# Codeshelf-0008.net
KiCad netlist of a schematic drawn in EAGLE
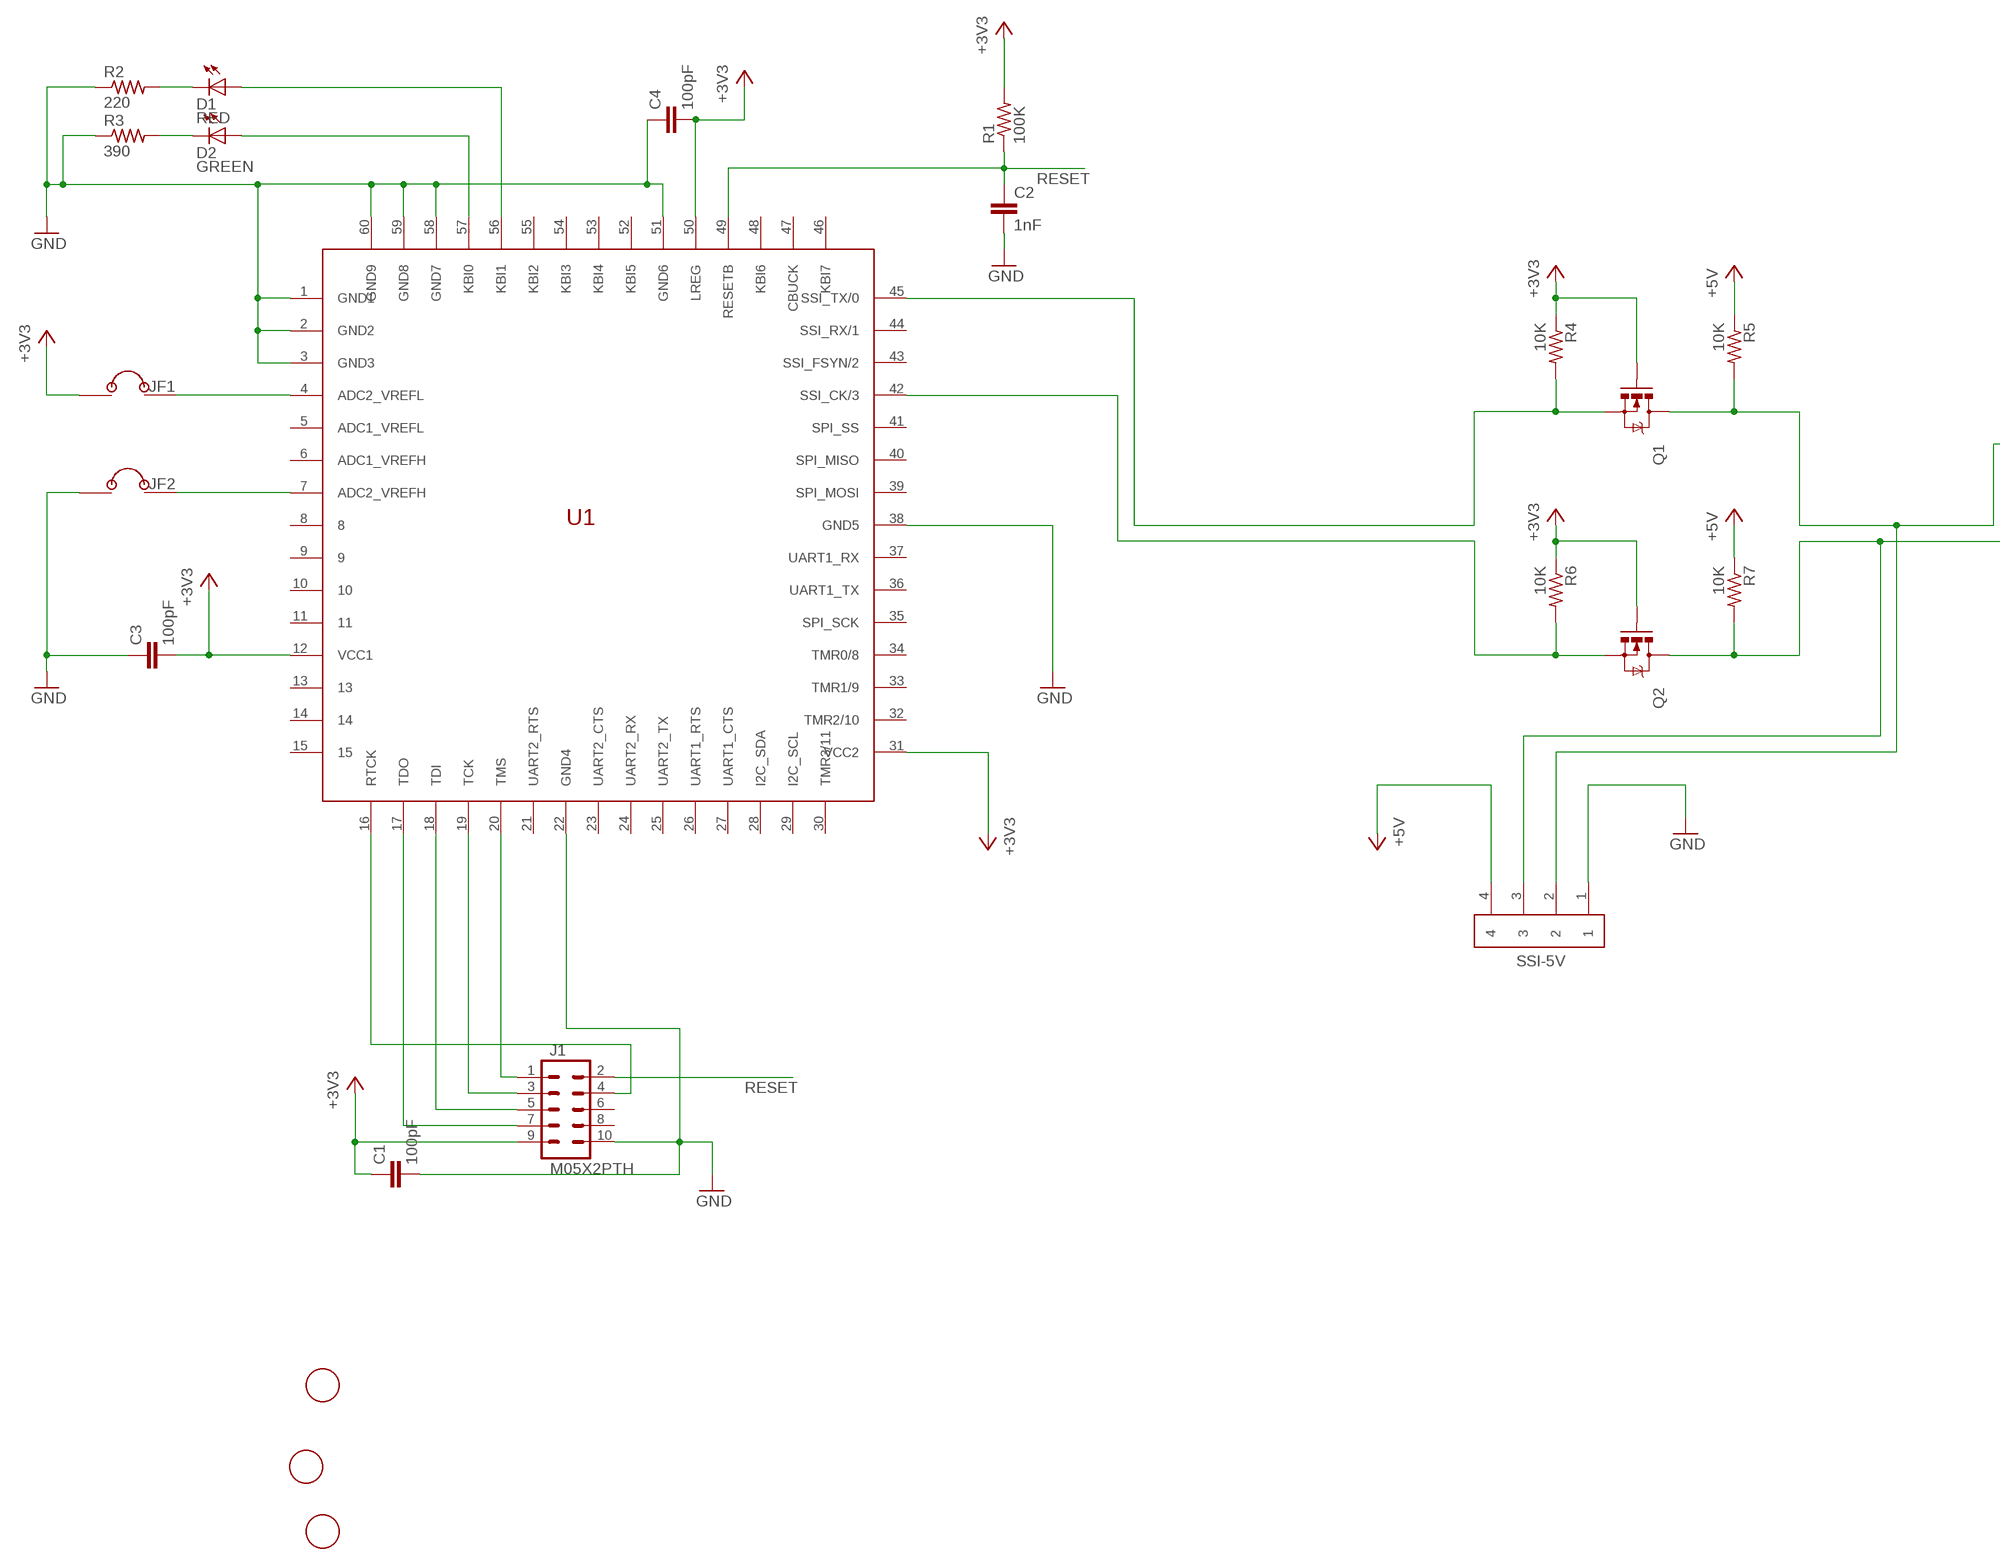
[diagram p0: schematic, sheet 1, part 1 of 2]
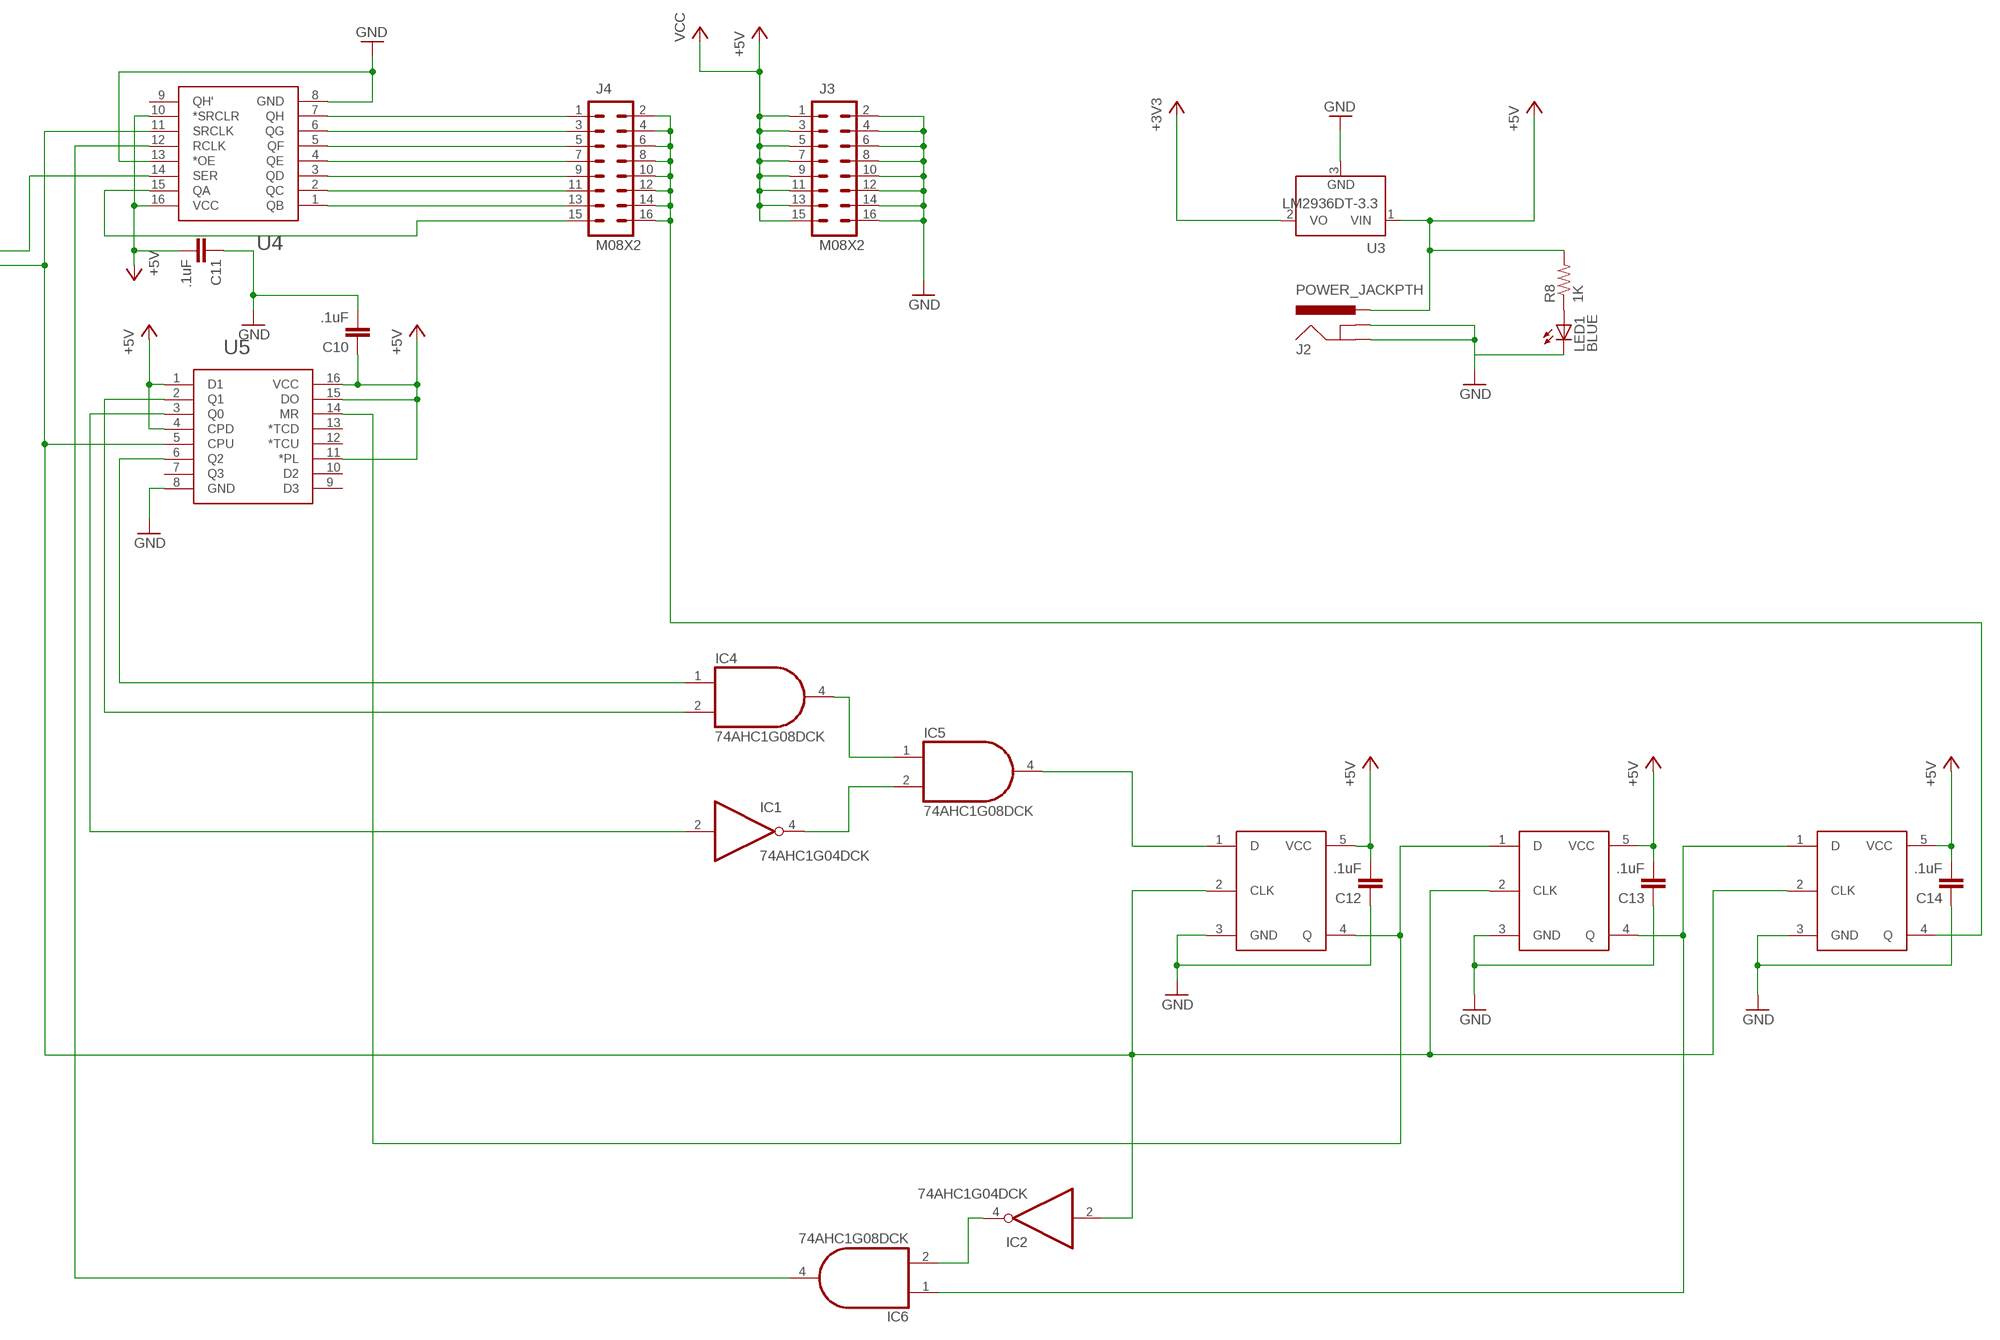
[diagram p1: schematic, sheet 1, part 2 of 2]

(export (version "E")
  (design (tool "Eeschema 10.0.6"))
  (components
    (comp (ref "C1")
      (value "100pF")
      (footprint "eagle-import:C0603")
      (libsource (lib "eagle-import") (part "RF-C0603"))
    )
    (comp (ref "C2")
      (value "1nF")
      (footprint "eagle-import:C0603")
      (libsource (lib "eagle-import") (part "RF-C0603"))
    )
    (comp (ref "C3")
      (value "100pF")
      (footprint "eagle-import:C0603")
      (libsource (lib "eagle-import") (part "RF-C0603"))
    )
    (comp (ref "C4")
      (value "100pF")
      (footprint "eagle-import:C0603")
      (libsource (lib "eagle-import") (part "RF-C0603"))
    )
    (comp (ref "C10")
      (value ".1uF")
      (footprint "eagle-import:C0402")
      (libsource (lib "eagle-import") (part "RF-C0402"))
    )
    (comp (ref "C11")
      (value ".1uF")
      (footprint "eagle-import:C0402")
      (libsource (lib "eagle-import") (part "RF-C0402"))
    )
    (comp (ref "C12")
      (value ".1uF")
      (footprint "eagle-import:C0402")
      (libsource (lib "eagle-import") (part "RF-C0402"))
    )
    (comp (ref "C13")
      (value ".1uF")
      (footprint "eagle-import:C0402")
      (libsource (lib "eagle-import") (part "RF-C0402"))
    )
    (comp (ref "C14")
      (value ".1uF")
      (footprint "eagle-import:C0402")
      (libsource (lib "eagle-import") (part "RF-C0402"))
    )
    (comp (ref "D1")
      (value "RED")
      (footprint "eagle-import:CHIP-LED0805")
      (libsource (lib "eagle-import") (part "LEDCHIP-LED0805"))
    )
    (comp (ref "D2")
      (value "GREEN")
      (footprint "eagle-import:CHIP-LED0805")
      (libsource (lib "eagle-import") (part "LEDCHIP-LED0805"))
    )
    (comp (ref "IC1")
      (value "74AHC1G04DCK")
      (footprint "eagle-import:SC70-5")
      (libsource (lib "eagle-import") (part "741G04DCKAHC"))
    )
    (comp (ref "IC2")
      (value "74AHC1G04DCK")
      (footprint "eagle-import:SC70-5")
      (libsource (lib "eagle-import") (part "741G04DCKAHC"))
    )
    (comp (ref "IC4")
      (value "74AHC1G08DCK")
      (footprint "eagle-import:SC70-5")
      (libsource (lib "eagle-import") (part "741G08DCKAHC"))
    )
    (comp (ref "IC5")
      (value "74AHC1G08DCK")
      (footprint "eagle-import:SC70-5")
      (libsource (lib "eagle-import") (part "741G08DCKAHC"))
    )
    (comp (ref "IC6")
      (value "74AHC1G08DCK")
      (footprint "eagle-import:SC70-5")
      (libsource (lib "eagle-import") (part "741G08DCKAHC"))
    )
    (comp (ref "J1")
      (value "M05X2PTH")
      (footprint "eagle-import:AVR_ICSP")
      (libsource (lib "eagle-import") (part "M05X2PTH"))
    )
    (comp (ref "J2")
      (value "POWER_JACKPTH")
      (footprint "eagle-import:POWER_JACK_PTH")
      (libsource (lib "eagle-import") (part "POWER_JACKPTH"))
    )
    (comp (ref "J3")
      (value "M08X2")
      (footprint "eagle-import:2X8")
      (libsource (lib "eagle-import") (part "M08X2"))
    )
    (comp (ref "J4")
      (value "M08X2")
      (footprint "eagle-import:2X8")
      (libsource (lib "eagle-import") (part "M08X2"))
    )
    (comp (ref "JF1")
      (value "JUMPER-2X-SMT-VIA")
      (footprint "eagle-import:JUMPER-VIA-2X")
      (libsource (lib "eagle-import") (part "JUMPER-2X-SMT-VIA"))
    )
    (comp (ref "JF2")
      (value "JUMPER-2X-SMT-VIA")
      (footprint "eagle-import:JUMPER-VIA-2X")
      (libsource (lib "eagle-import") (part "JUMPER-2X-SMT-VIA"))
    )
    (comp (ref "LED1")
      (value "BLUE")
      (footprint "eagle-import:LED5MM")
      (libsource (lib "eagle-import") (part "LED5MM"))
    )
    (comp (ref "Q1")
      (value "MOSFET-NCHANNELBSS138")
      (footprint "eagle-import:SOT23")
      (libsource (lib "eagle-import") (part "MOSFET-NCHANNELBSS138"))
    )
    (comp (ref "Q2")
      (value "MOSFET-NCHANNELBSS138")
      (footprint "eagle-import:SOT23")
      (libsource (lib "eagle-import") (part "MOSFET-NCHANNELBSS138"))
    )
    (comp (ref "R1")
      (value "100K")
      (footprint "eagle-import:RF-R0402")
      (libsource (lib "eagle-import") (part "RF-R0402"))
    )
    (comp (ref "R2")
      (value "220")
      (footprint "eagle-import:RF-R0402")
      (libsource (lib "eagle-import") (part "RF-R0402"))
    )
    (comp (ref "R3")
      (value "390")
      (footprint "eagle-import:RF-R0402")
      (libsource (lib "eagle-import") (part "RF-R0402"))
    )
    (comp (ref "R4")
      (value "10K")
      (footprint "eagle-import:RF-R0402")
      (libsource (lib "eagle-import") (part "RF-R0402"))
    )
    (comp (ref "R5")
      (value "10K")
      (footprint "eagle-import:RF-R0402")
      (libsource (lib "eagle-import") (part "RF-R0402"))
    )
    (comp (ref "R6")
      (value "10K")
      (footprint "eagle-import:RF-R0402")
      (libsource (lib "eagle-import") (part "RF-R0402"))
    )
    (comp (ref "R7")
      (value "10K")
      (footprint "eagle-import:RF-R0402")
      (libsource (lib "eagle-import") (part "RF-R0402"))
    )
    (comp (ref "R8")
      (value "1K")
      (footprint "eagle-import:0204_7")
      (libsource (lib "eagle-import") (part "R-US_0204/7"))
    )
    (comp (ref "SSI-5V")
      (value "HEADER-4X39357")
      (footprint "eagle-import:MOLEX-39357-0004")
      (libsource (lib "eagle-import") (part "HEADER-4X39357"))
    )
    (comp (ref "U$2")
      (value "FIDUCIAL")
      (footprint "eagle-import:FIDUCIAL_1MM")
      (libsource (lib "eagle-import") (part "FIDUCIAL"))
    )
    (comp (ref "U$3")
      (value "FIDUCIAL")
      (footprint "eagle-import:FIDUCIAL_1MM")
      (libsource (lib "eagle-import") (part "FIDUCIAL"))
    )
    (comp (ref "U$4")
      (value "FIDUCIAL")
      (footprint "eagle-import:FIDUCIAL_1MM")
      (libsource (lib "eagle-import") (part "FIDUCIAL"))
    )
    (comp (ref "U1")
      (value "ZSFM201-1A")
      (footprint "eagle-import:ZSFM201-1")
      (libsource (lib "eagle-import") (part "ZSFM201-1A"))
    )
    (comp (ref "U3")
      (value "LM2936DT-3.3")
      (footprint "eagle-import:TO252")
      (fields (field (name "MPN") "LM2936DT-3.3."))
      (libsource (lib "eagle-import") (part "LM2936?DT-3.3"))
    )
    (comp (ref "U4")
      (value "SN74HC595PW")
      (footprint "eagle-import:TSSOP16")
      (libsource (lib "eagle-import") (part "SN74HC595PW"))
    )
    (comp (ref "U5")
      (value "74HCT193PW")
      (footprint "eagle-import:TSSOP16")
      (libsource (lib "eagle-import") (part "74HCT193PW"))
    )
    (comp (ref "U6")
      (value "D-FLIP-FLOP-74LV1G79DBVR")
      (footprint "eagle-import:SOT23-5")
      (libsource (lib "eagle-import") (part "D-FLIP-FLOP-74LV1G79DBVR"))
    )
    (comp (ref "U7")
      (value "D-FLIP-FLOP-74LV1G79DBVR")
      (footprint "eagle-import:SOT23-5")
      (libsource (lib "eagle-import") (part "D-FLIP-FLOP-74LV1G79DBVR"))
    )
    (comp (ref "U8")
      (value "D-FLIP-FLOP-74LV1G79DBVR")
      (footprint "eagle-import:SOT23-5")
      (libsource (lib "eagle-import") (part "D-FLIP-FLOP-74LV1G79DBVR"))
    )
  )
  (nets
    (net (code "1") (name "+3V3") (class "Default")
      (node (ref "C1") (pin "1") (pinfunction "1_1") (pintype "passive"))
      (node (ref "C3") (pin "2") (pinfunction "2_2") (pintype "passive"))
      (node (ref "C4") (pin "2") (pinfunction "2_2") (pintype "passive"))
      (node (ref "J1") (pin "9") (pinfunction "9_9") (pintype "passive"))
      (node (ref "JF1") (pin "1") (pinfunction "1_1") (pintype "bidirectional"))
      (node (ref "Q1") (pin "1") (pinfunction "G_1") (pintype "passive"))
      (node (ref "Q2") (pin "1") (pinfunction "G_1") (pintype "passive"))
      (node (ref "R1") (pin "2") (pinfunction "2_2") (pintype "passive"))
      (node (ref "R4") (pin "1") (pinfunction "1_1") (pintype "passive"))
      (node (ref "R6") (pin "1") (pinfunction "1_1") (pintype "passive"))
      (node (ref "U1") (pin "12") (pinfunction "VCC1_12") (pintype "power_in"))
      (node (ref "U1") (pin "31") (pinfunction "VCC2_31") (pintype "power_in"))
      (node (ref "U1") (pin "50") (pinfunction "LREG_50") (pintype "bidirectional"))
      (node (ref "U3") (pin "2") (pinfunction "VO_2") (pintype "passive"))
    )
    (net (code "2") (name "+5V") (class "Default")
      (node (ref "C10") (pin "1") (pinfunction "1_1") (pintype "passive"))
      (node (ref "C11") (pin "2") (pinfunction "2_2") (pintype "passive"))
      (node (ref "C12") (pin "2") (pinfunction "2_2") (pintype "passive"))
      (node (ref "C13") (pin "2") (pinfunction "2_2") (pintype "passive"))
      (node (ref "C14") (pin "2") (pinfunction "2_2") (pintype "passive"))
      (node (ref "J2") (pin "PWR") (pinfunction "PWR_PWR") (pintype "bidirectional"))
      (node (ref "J3") (pin "1") (pinfunction "1_1") (pintype "passive"))
      (node (ref "J3") (pin "11") (pinfunction "11_11") (pintype "passive"))
      (node (ref "J3") (pin "13") (pinfunction "13_13") (pintype "passive"))
      (node (ref "J3") (pin "15") (pinfunction "15_15") (pintype "passive"))
      (node (ref "J3") (pin "3") (pinfunction "3_3") (pintype "passive"))
      (node (ref "J3") (pin "5") (pinfunction "5_5") (pintype "passive"))
      (node (ref "J3") (pin "7") (pinfunction "7_7") (pintype "passive"))
      (node (ref "J3") (pin "9") (pinfunction "9_9") (pintype "passive"))
      (node (ref "R5") (pin "1") (pinfunction "1_1") (pintype "passive"))
      (node (ref "R7") (pin "1") (pinfunction "1_1") (pintype "passive"))
      (node (ref "R8") (pin "2") (pinfunction "2_2") (pintype "passive"))
      (node (ref "SSI-5V") (pin "4") (pinfunction "4_4") (pintype "bidirectional"))
      (node (ref "U3") (pin "1") (pinfunction "VIN_1") (pintype "input"))
      (node (ref "U4") (pin "10") (pinfunction "*SRCLR_10") (pintype "bidirectional"))
      (node (ref "U4") (pin "16") (pinfunction "VCC_16") (pintype "bidirectional"))
      (node (ref "U5") (pin "1") (pinfunction "D1_1") (pintype "bidirectional"))
      (node (ref "U5") (pin "11") (pinfunction "*PL_11") (pintype "bidirectional"))
      (node (ref "U5") (pin "15") (pinfunction "DO_15") (pintype "bidirectional"))
      (node (ref "U5") (pin "16") (pinfunction "VCC_16") (pintype "power_in"))
      (node (ref "U5") (pin "4") (pinfunction "CPD_4") (pintype "bidirectional"))
      (node (ref "U6") (pin "5") (pinfunction "VCC_5") (pintype "bidirectional"))
      (node (ref "U7") (pin "5") (pinfunction "VCC_5") (pintype "bidirectional"))
      (node (ref "U8") (pin "5") (pinfunction "VCC_5") (pintype "bidirectional"))
    )
    (net (code "3") (name "/RESET") (class "Default")
      (node (ref "C2") (pin "1") (pinfunction "1_1") (pintype "passive"))
      (node (ref "J1") (pin "2") (pinfunction "2_2") (pintype "passive"))
      (node (ref "R1") (pin "1") (pinfunction "1_1") (pintype "passive"))
      (node (ref "U1") (pin "49") (pinfunction "RESETB_49") (pintype "bidirectional"))
    )
    (net (code "4") (name "GND") (class "Default")
      (node (ref "C1") (pin "2") (pinfunction "2_2") (pintype "passive"))
      (node (ref "C10") (pin "2") (pinfunction "2_2") (pintype "passive"))
      (node (ref "C11") (pin "1") (pinfunction "1_1") (pintype "passive"))
      (node (ref "C12") (pin "1") (pinfunction "1_1") (pintype "passive"))
      (node (ref "C13") (pin "1") (pinfunction "1_1") (pintype "passive"))
      (node (ref "C14") (pin "1") (pinfunction "1_1") (pintype "passive"))
      (node (ref "C2") (pin "2") (pinfunction "2_2") (pintype "passive"))
      (node (ref "C3") (pin "1") (pinfunction "1_1") (pintype "passive"))
      (node (ref "C4") (pin "1") (pinfunction "1_1") (pintype "passive"))
      (node (ref "J1") (pin "10") (pinfunction "10_10") (pintype "passive"))
      (node (ref "J2") (pin "GND") (pinfunction "GND_GND") (pintype "bidirectional"))
      (node (ref "J2") (pin "GNDBREAK") (pinfunction "GNDBREAK_GNDBREAK") (pintype "bidirectional"))
      (node (ref "J3") (pin "10") (pinfunction "10_10") (pintype "passive"))
      (node (ref "J3") (pin "12") (pinfunction "12_12") (pintype "passive"))
      (node (ref "J3") (pin "14") (pinfunction "14_14") (pintype "passive"))
      (node (ref "J3") (pin "16") (pinfunction "16_16") (pintype "passive"))
      (node (ref "J3") (pin "2") (pinfunction "2_2") (pintype "passive"))
      (node (ref "J3") (pin "4") (pinfunction "4_4") (pintype "passive"))
      (node (ref "J3") (pin "6") (pinfunction "6_6") (pintype "passive"))
      (node (ref "J3") (pin "8") (pinfunction "8_8") (pintype "passive"))
      (node (ref "JF2") (pin "1") (pinfunction "1_1") (pintype "bidirectional"))
      (node (ref "LED1") (pin "K") (pinfunction "C_K") (pintype "passive"))
      (node (ref "R2") (pin "1") (pinfunction "1_1") (pintype "passive"))
      (node (ref "R3") (pin "1") (pinfunction "1_1") (pintype "passive"))
      (node (ref "SSI-5V") (pin "1") (pinfunction "1_1") (pintype "bidirectional"))
      (node (ref "U1") (pin "1") (pinfunction "GND1_1") (pintype "power_in"))
      (node (ref "U1") (pin "2") (pinfunction "GND2_2") (pintype "power_in"))
      (node (ref "U1") (pin "22") (pinfunction "GND4_22") (pintype "power_in"))
      (node (ref "U1") (pin "3") (pinfunction "GND3_3") (pintype "power_in"))
      (node (ref "U1") (pin "38") (pinfunction "GND5_38") (pintype "power_in"))
      (node (ref "U1") (pin "51") (pinfunction "GND6_51") (pintype "power_in"))
      (node (ref "U1") (pin "58") (pinfunction "GND7_58") (pintype "power_in"))
      (node (ref "U1") (pin "59") (pinfunction "GND8_59") (pintype "power_in"))
      (node (ref "U1") (pin "60") (pinfunction "GND9_60") (pintype "power_in"))
      (node (ref "U3") (pin "3") (pinfunction "GND_3") (pintype "passive"))
      (node (ref "U4") (pin "13") (pinfunction "*OE_13") (pintype "bidirectional"))
      (node (ref "U4") (pin "8") (pinfunction "GND_8") (pintype "bidirectional"))
      (node (ref "U5") (pin "8") (pinfunction "GND_8") (pintype "power_in"))
      (node (ref "U6") (pin "3") (pinfunction "GND_3") (pintype "bidirectional"))
      (node (ref "U7") (pin "3") (pinfunction "GND_3") (pintype "bidirectional"))
      (node (ref "U8") (pin "3") (pinfunction "GND_3") (pintype "bidirectional"))
    )
    (net (code "5") (name "Net-(D1-PadC)") (class "Default")
      (node (ref "D1") (pin "C") (pinfunction "C_C") (pintype "passive"))
      (node (ref "R2") (pin "2") (pinfunction "2_2") (pintype "passive"))
    )
    (net (code "6") (name "Net-(D2-PadC)") (class "Default")
      (node (ref "D2") (pin "C") (pinfunction "C_C") (pintype "passive"))
      (node (ref "R3") (pin "2") (pinfunction "2_2") (pintype "passive"))
    )
    (net (code "7") (name "Net-(IC1A-I)") (class "Default")
      (node (ref "IC1") (pin "2") (pinfunction "I_2") (pintype "input"))
      (node (ref "U5") (pin "3") (pinfunction "Q0_3") (pintype "bidirectional"))
    )
    (net (code "8") (name "Net-(IC1A-O)") (class "Default")
      (node (ref "IC1") (pin "4") (pinfunction "O_4") (pintype "output"))
      (node (ref "IC5") (pin "2") (pinfunction "I1_2") (pintype "input"))
    )
    (net (code "9") (name "Net-(IC2A-I)") (class "Default")
      (node (ref "IC2") (pin "2") (pinfunction "I_2") (pintype "input"))
      (node (ref "Q2") (pin "3") (pinfunction "D_3") (pintype "passive"))
      (node (ref "R7") (pin "2") (pinfunction "2_2") (pintype "passive"))
      (node (ref "SSI-5V") (pin "3") (pinfunction "3_3") (pintype "bidirectional"))
      (node (ref "U4") (pin "11") (pinfunction "SRCLK_11") (pintype "bidirectional"))
      (node (ref "U5") (pin "5") (pinfunction "CPU_5") (pintype "bidirectional"))
      (node (ref "U6") (pin "2") (pinfunction "CLK_2") (pintype "bidirectional"))
      (node (ref "U7") (pin "2") (pinfunction "CLK_2") (pintype "bidirectional"))
      (node (ref "U8") (pin "2") (pinfunction "CLK_2") (pintype "bidirectional"))
    )
    (net (code "10") (name "Net-(IC2A-O)") (class "Default")
      (node (ref "IC2") (pin "4") (pinfunction "O_4") (pintype "output"))
      (node (ref "IC6") (pin "2") (pinfunction "I1_2") (pintype "input"))
    )
    (net (code "11") (name "Net-(IC4A-I0)") (class "Default")
      (node (ref "IC4") (pin "1") (pinfunction "I0_1") (pintype "input"))
      (node (ref "U5") (pin "6") (pinfunction "Q2_6") (pintype "bidirectional"))
    )
    (net (code "12") (name "Net-(IC4A-I1)") (class "Default")
      (node (ref "IC4") (pin "2") (pinfunction "I1_2") (pintype "input"))
      (node (ref "U5") (pin "2") (pinfunction "Q1_2") (pintype "bidirectional"))
    )
    (net (code "13") (name "Net-(IC4A-O)") (class "Default")
      (node (ref "IC4") (pin "4") (pinfunction "O_4") (pintype "output"))
      (node (ref "IC5") (pin "1") (pinfunction "I0_1") (pintype "input"))
    )
    (net (code "14") (name "Net-(IC5A-O)") (class "Default")
      (node (ref "IC5") (pin "4") (pinfunction "O_4") (pintype "output"))
      (node (ref "U6") (pin "1") (pinfunction "D_1") (pintype "bidirectional"))
    )
    (net (code "15") (name "Net-(IC6A-I0)") (class "Default")
      (node (ref "IC6") (pin "1") (pinfunction "I0_1") (pintype "input"))
      (node (ref "U7") (pin "4") (pinfunction "Q_4") (pintype "bidirectional"))
      (node (ref "U8") (pin "1") (pinfunction "D_1") (pintype "bidirectional"))
    )
    (net (code "16") (name "Net-(IC6A-O)") (class "Default")
      (node (ref "IC6") (pin "4") (pinfunction "O_4") (pintype "output"))
      (node (ref "U4") (pin "12") (pinfunction "RCLK_12") (pintype "bidirectional"))
    )
    (net (code "17") (name "Net-(LED1-PadA)") (class "Default")
      (node (ref "LED1") (pin "A") (pinfunction "A_A") (pintype "passive"))
      (node (ref "R8") (pin "1") (pinfunction "1_1") (pintype "passive"))
    )
    (net (code "18") (name "Net-(Q1-D)") (class "Default")
      (node (ref "Q1") (pin "3") (pinfunction "D_3") (pintype "passive"))
      (node (ref "R5") (pin "2") (pinfunction "2_2") (pintype "passive"))
      (node (ref "SSI-5V") (pin "2") (pinfunction "2_2") (pintype "bidirectional"))
      (node (ref "U4") (pin "14") (pinfunction "SER_14") (pintype "bidirectional"))
    )
    (net (code "19") (name "Net-(Q1-S)") (class "Default")
      (node (ref "Q1") (pin "2") (pinfunction "S_2") (pintype "passive"))
      (node (ref "R4") (pin "2") (pinfunction "2_2") (pintype "passive"))
      (node (ref "U1") (pin "45") (pinfunction "SSI_TX/0_45") (pintype "bidirectional"))
    )
    (net (code "20") (name "Net-(Q2-S)") (class "Default")
      (node (ref "Q2") (pin "2") (pinfunction "S_2") (pintype "passive"))
      (node (ref "R6") (pin "2") (pinfunction "2_2") (pintype "passive"))
      (node (ref "U1") (pin "42") (pinfunction "SSI_CK/3_42") (pintype "bidirectional"))
    )
    (net (code "21") (name "Net-(U1-ADC2_VREFH)") (class "Default")
      (node (ref "JF2") (pin "2") (pinfunction "2_2") (pintype "bidirectional"))
      (node (ref "U1") (pin "7") (pinfunction "ADC2_VREFH_7") (pintype "bidirectional"))
    )
    (net (code "22") (name "Net-(U1-ADC2_VREFL)") (class "Default")
      (node (ref "JF1") (pin "2") (pinfunction "2_2") (pintype "bidirectional"))
      (node (ref "U1") (pin "4") (pinfunction "ADC2_VREFL_4") (pintype "bidirectional"))
    )
    (net (code "23") (name "Net-(U1-KBI0)") (class "Default")
      (node (ref "D2") (pin "A") (pinfunction "A_A") (pintype "passive"))
      (node (ref "U1") (pin "57") (pinfunction "KBI0_57") (pintype "bidirectional"))
    )
    (net (code "24") (name "Net-(U1-KBI1)") (class "Default")
      (node (ref "D1") (pin "A") (pinfunction "A_A") (pintype "passive"))
      (node (ref "U1") (pin "56") (pinfunction "KBI1_56") (pintype "bidirectional"))
    )
    (net (code "25") (name "Net-(U1-RTCK)") (class "Default")
      (node (ref "J1") (pin "4") (pinfunction "4_4") (pintype "passive"))
      (node (ref "U1") (pin "16") (pinfunction "RTCK_16") (pintype "bidirectional"))
    )
    (net (code "26") (name "Net-(U1-TCK)") (class "Default")
      (node (ref "J1") (pin "3") (pinfunction "3_3") (pintype "passive"))
      (node (ref "U1") (pin "19") (pinfunction "TCK_19") (pintype "bidirectional"))
    )
    (net (code "27") (name "Net-(U1-TDI)") (class "Default")
      (node (ref "J1") (pin "5") (pinfunction "5_5") (pintype "passive"))
      (node (ref "U1") (pin "18") (pinfunction "TDI_18") (pintype "bidirectional"))
    )
    (net (code "28") (name "Net-(U1-TDO)") (class "Default")
      (node (ref "J1") (pin "7") (pinfunction "7_7") (pintype "passive"))
      (node (ref "U1") (pin "17") (pinfunction "TDO_17") (pintype "bidirectional"))
    )
    (net (code "29") (name "Net-(U1-TMS)") (class "Default")
      (node (ref "J1") (pin "1") (pinfunction "1_1") (pintype "passive"))
      (node (ref "U1") (pin "20") (pinfunction "TMS_20") (pintype "bidirectional"))
    )
    (net (code "30") (name "Net-(U4-QA)") (class "Default")
      (node (ref "J4") (pin "15") (pinfunction "15_15") (pintype "passive"))
      (node (ref "U4") (pin "15") (pinfunction "QA_15") (pintype "bidirectional"))
    )
    (net (code "31") (name "Net-(U4-QB)") (class "Default")
      (node (ref "J4") (pin "13") (pinfunction "13_13") (pintype "passive"))
      (node (ref "U4") (pin "1") (pinfunction "QB_1") (pintype "bidirectional"))
    )
    (net (code "32") (name "Net-(U4-QC)") (class "Default")
      (node (ref "J4") (pin "11") (pinfunction "11_11") (pintype "passive"))
      (node (ref "U4") (pin "2") (pinfunction "QC_2") (pintype "bidirectional"))
    )
    (net (code "33") (name "Net-(U4-QD)") (class "Default")
      (node (ref "J4") (pin "9") (pinfunction "9_9") (pintype "passive"))
      (node (ref "U4") (pin "3") (pinfunction "QD_3") (pintype "bidirectional"))
    )
    (net (code "34") (name "Net-(U4-QE)") (class "Default")
      (node (ref "J4") (pin "7") (pinfunction "7_7") (pintype "passive"))
      (node (ref "U4") (pin "4") (pinfunction "QE_4") (pintype "bidirectional"))
    )
    (net (code "35") (name "Net-(U4-QF)") (class "Default")
      (node (ref "J4") (pin "5") (pinfunction "5_5") (pintype "passive"))
      (node (ref "U4") (pin "5") (pinfunction "QF_5") (pintype "bidirectional"))
    )
    (net (code "36") (name "Net-(U4-QG)") (class "Default")
      (node (ref "J4") (pin "3") (pinfunction "3_3") (pintype "passive"))
      (node (ref "U4") (pin "6") (pinfunction "QG_6") (pintype "bidirectional"))
    )
    (net (code "37") (name "Net-(U4-QH)") (class "Default")
      (node (ref "J4") (pin "1") (pinfunction "1_1") (pintype "passive"))
      (node (ref "U4") (pin "7") (pinfunction "QH_7") (pintype "bidirectional"))
    )
    (net (code "38") (name "Net-(U5-MR)") (class "Default")
      (node (ref "U5") (pin "14") (pinfunction "MR_14") (pintype "bidirectional"))
      (node (ref "U6") (pin "4") (pinfunction "Q_4") (pintype "bidirectional"))
      (node (ref "U7") (pin "1") (pinfunction "D_1") (pintype "bidirectional"))
    )
    (net (code "39") (name "Net-(U8-Q)") (class "Default")
      (node (ref "J4") (pin "10") (pinfunction "10_10") (pintype "passive"))
      (node (ref "J4") (pin "12") (pinfunction "12_12") (pintype "passive"))
      (node (ref "J4") (pin "14") (pinfunction "14_14") (pintype "passive"))
      (node (ref "J4") (pin "16") (pinfunction "16_16") (pintype "passive"))
      (node (ref "J4") (pin "2") (pinfunction "2_2") (pintype "passive"))
      (node (ref "J4") (pin "4") (pinfunction "4_4") (pintype "passive"))
      (node (ref "J4") (pin "6") (pinfunction "6_6") (pintype "passive"))
      (node (ref "J4") (pin "8") (pinfunction "8_8") (pintype "passive"))
      (node (ref "U8") (pin "4") (pinfunction "Q_4") (pintype "bidirectional"))
    )
    (net (code "40") (name "unconnected-(J1-Pad6)") (class "Default")
      (node (ref "J1") (pin "6") (pinfunction "6_6") (pintype "passive"))
    )
    (net (code "41") (name "unconnected-(J1-Pad8)") (class "Default")
      (node (ref "J1") (pin "8") (pinfunction "8_8") (pintype "passive"))
    )
    (net (code "42") (name "unconnected-(U1-ADC1_VREFH-Pad6)") (class "Default")
      (node (ref "U1") (pin "6") (pinfunction "ADC1_VREFH_6") (pintype "bidirectional"))
    )
    (net (code "43") (name "unconnected-(U1-ADC1_VREFL-Pad5)") (class "Default")
      (node (ref "U1") (pin "5") (pinfunction "ADC1_VREFL_5") (pintype "bidirectional"))
    )
    (net (code "44") (name "unconnected-(U1-CBUCK-Pad47)") (class "Default")
      (node (ref "U1") (pin "47") (pinfunction "CBUCK_47") (pintype "bidirectional"))
    )
    (net (code "45") (name "unconnected-(U1-I2C_SCL-Pad29)") (class "Default")
      (node (ref "U1") (pin "29") (pinfunction "I2C_SCL_29") (pintype "bidirectional"))
    )
    (net (code "46") (name "unconnected-(U1-I2C_SDA-Pad28)") (class "Default")
      (node (ref "U1") (pin "28") (pinfunction "I2C_SDA_28") (pintype "bidirectional"))
    )
    (net (code "47") (name "unconnected-(U1-KBI2-Pad55)") (class "Default")
      (node (ref "U1") (pin "55") (pinfunction "KBI2_55") (pintype "bidirectional"))
    )
    (net (code "48") (name "unconnected-(U1-KBI3-Pad54)") (class "Default")
      (node (ref "U1") (pin "54") (pinfunction "KBI3_54") (pintype "bidirectional"))
    )
    (net (code "49") (name "unconnected-(U1-KBI4-Pad53)") (class "Default")
      (node (ref "U1") (pin "53") (pinfunction "KBI4_53") (pintype "bidirectional"))
    )
    (net (code "50") (name "unconnected-(U1-KBI5-Pad52)") (class "Default")
      (node (ref "U1") (pin "52") (pinfunction "KBI5_52") (pintype "bidirectional"))
    )
    (net (code "51") (name "unconnected-(U1-KBI6-Pad48)") (class "Default")
      (node (ref "U1") (pin "48") (pinfunction "KBI6_48") (pintype "bidirectional"))
    )
    (net (code "52") (name "unconnected-(U1-KBI7-Pad46)") (class "Default")
      (node (ref "U1") (pin "46") (pinfunction "KBI7_46") (pintype "bidirectional"))
    )
    (net (code "53") (name "unconnected-(U1-Pad8)") (class "Default")
      (node (ref "U1") (pin "8") (pinfunction "8_8") (pintype "bidirectional"))
    )
    (net (code "54") (name "unconnected-(U1-Pad9)") (class "Default")
      (node (ref "U1") (pin "9") (pinfunction "9_9") (pintype "bidirectional"))
    )
    (net (code "55") (name "unconnected-(U1-Pad10)") (class "Default")
      (node (ref "U1") (pin "10") (pinfunction "10_10") (pintype "bidirectional"))
    )
    (net (code "56") (name "unconnected-(U1-Pad11)") (class "Default")
      (node (ref "U1") (pin "11") (pinfunction "11_11") (pintype "bidirectional"))
    )
    (net (code "57") (name "unconnected-(U1-Pad13)") (class "Default")
      (node (ref "U1") (pin "13") (pinfunction "13_13") (pintype "bidirectional"))
    )
    (net (code "58") (name "unconnected-(U1-Pad14)") (class "Default")
      (node (ref "U1") (pin "14") (pinfunction "14_14") (pintype "bidirectional"))
    )
    (net (code "59") (name "unconnected-(U1-Pad15)") (class "Default")
      (node (ref "U1") (pin "15") (pinfunction "15_15") (pintype "bidirectional"))
    )
    (net (code "60") (name "unconnected-(U1-SPI_MISO-Pad40)") (class "Default")
      (node (ref "U1") (pin "40") (pinfunction "SPI_MISO_40") (pintype "bidirectional"))
    )
    (net (code "61") (name "unconnected-(U1-SPI_MOSI-Pad39)") (class "Default")
      (node (ref "U1") (pin "39") (pinfunction "SPI_MOSI_39") (pintype "bidirectional"))
    )
    (net (code "62") (name "unconnected-(U1-SPI_SCK-Pad35)") (class "Default")
      (node (ref "U1") (pin "35") (pinfunction "SPI_SCK_35") (pintype "bidirectional"))
    )
    (net (code "63") (name "unconnected-(U1-SPI_SS-Pad41)") (class "Default")
      (node (ref "U1") (pin "41") (pinfunction "SPI_SS_41") (pintype "bidirectional"))
    )
    (net (code "64") (name "unconnected-(U1-SSI_FSYN{slash}2-Pad43)") (class "Default")
      (node (ref "U1") (pin "43") (pinfunction "SSI_FSYN/2_43") (pintype "bidirectional"))
    )
    (net (code "65") (name "unconnected-(U1-SSI_RX{slash}1-Pad44)") (class "Default")
      (node (ref "U1") (pin "44") (pinfunction "SSI_RX/1_44") (pintype "bidirectional"))
    )
    (net (code "66") (name "unconnected-(U1-TMR0{slash}8-Pad34)") (class "Default")
      (node (ref "U1") (pin "34") (pinfunction "TMR0/8_34") (pintype "bidirectional"))
    )
    (net (code "67") (name "unconnected-(U1-TMR1{slash}9-Pad33)") (class "Default")
      (node (ref "U1") (pin "33") (pinfunction "TMR1/9_33") (pintype "bidirectional"))
    )
    (net (code "68") (name "unconnected-(U1-TMR2{slash}10-Pad32)") (class "Default")
      (node (ref "U1") (pin "32") (pinfunction "TMR2/10_32") (pintype "bidirectional"))
    )
    (net (code "69") (name "unconnected-(U1-TMR3{slash}11-Pad30)") (class "Default")
      (node (ref "U1") (pin "30") (pinfunction "TMR3/11_30") (pintype "bidirectional"))
    )
    (net (code "70") (name "unconnected-(U1-UART1_CTS-Pad27)") (class "Default")
      (node (ref "U1") (pin "27") (pinfunction "UART1_CTS_27") (pintype "bidirectional"))
    )
    (net (code "71") (name "unconnected-(U1-UART1_RTS-Pad26)") (class "Default")
      (node (ref "U1") (pin "26") (pinfunction "UART1_RTS_26") (pintype "bidirectional"))
    )
    (net (code "72") (name "unconnected-(U1-UART1_RX-Pad37)") (class "Default")
      (node (ref "U1") (pin "37") (pinfunction "UART1_RX_37") (pintype "bidirectional"))
    )
    (net (code "73") (name "unconnected-(U1-UART1_TX-Pad36)") (class "Default")
      (node (ref "U1") (pin "36") (pinfunction "UART1_TX_36") (pintype "bidirectional"))
    )
    (net (code "74") (name "unconnected-(U1-UART2_CTS-Pad23)") (class "Default")
      (node (ref "U1") (pin "23") (pinfunction "UART2_CTS_23") (pintype "bidirectional"))
    )
    (net (code "75") (name "unconnected-(U1-UART2_RTS-Pad21)") (class "Default")
      (node (ref "U1") (pin "21") (pinfunction "UART2_RTS_21") (pintype "bidirectional"))
    )
    (net (code "76") (name "unconnected-(U1-UART2_RX-Pad24)") (class "Default")
      (node (ref "U1") (pin "24") (pinfunction "UART2_RX_24") (pintype "bidirectional"))
    )
    (net (code "77") (name "unconnected-(U1-UART2_TX-Pad25)") (class "Default")
      (node (ref "U1") (pin "25") (pinfunction "UART2_TX_25") (pintype "bidirectional"))
    )
    (net (code "78") (name "unconnected-(U4-QH'-Pad9)") (class "Default")
      (node (ref "U4") (pin "9") (pinfunction "QH'_9") (pintype "bidirectional"))
    )
    (net (code "79") (name "unconnected-(U5-*TCD-Pad13)") (class "Default")
      (node (ref "U5") (pin "13") (pinfunction "*TCD_13") (pintype "bidirectional"))
    )
    (net (code "80") (name "unconnected-(U5-*TCU-Pad12)") (class "Default")
      (node (ref "U5") (pin "12") (pinfunction "*TCU_12") (pintype "bidirectional"))
    )
    (net (code "81") (name "unconnected-(U5-D2-Pad10)") (class "Default")
      (node (ref "U5") (pin "10") (pinfunction "D2_10") (pintype "bidirectional"))
    )
    (net (code "82") (name "unconnected-(U5-D3-Pad9)") (class "Default")
      (node (ref "U5") (pin "9") (pinfunction "D3_9") (pintype "bidirectional"))
    )
    (net (code "83") (name "unconnected-(U5-Q3-Pad7)") (class "Default")
      (node (ref "U5") (pin "7") (pinfunction "Q3_7") (pintype "bidirectional"))
    )
  )
)
